# Pinout_DevKitC_Sch.net
KiCad netlist of a schematic drawn in Altium Designer
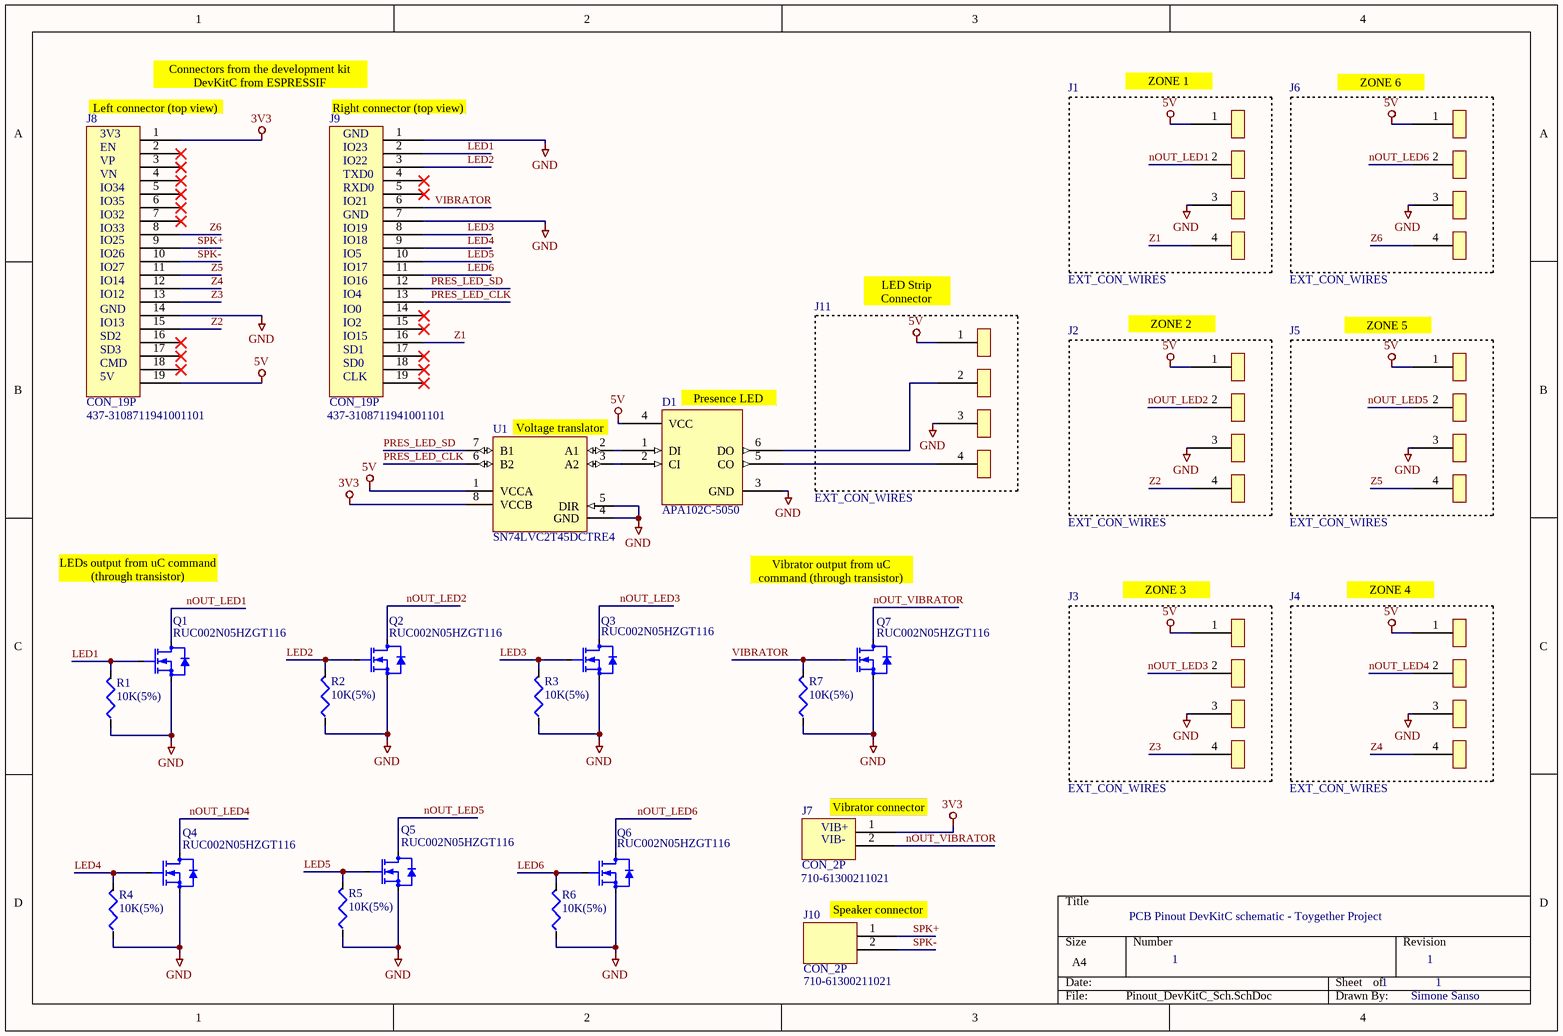
[diagram p0: Pinout_DevKitC_Sch.SchDoc]

(export (version "E")
  (design (tool "Eeschema 10.0.6"))
  (components
    (comp (ref "D1")
      (value "APA102C-5050")
      (footprint "APA102C-5050")
      (libsource (lib "Toygether_Schlib") (part "APA102C"))
    )
    (comp (ref "J1")
      (value "EXT_CON_WIRES")
      (footprint "EXT_CON_WIRES_4P")
      (description "Pads between pinout board and wires of the plush toy")
      (libsource (lib "Toygether_Schlib") (part "EXT_CON_WIRES"))
    )
    (comp (ref "J2")
      (value "EXT_CON_WIRES")
      (footprint "EXT_CON_WIRES_4P")
      (description "Pads between pinout board and wires of the plush toy")
      (libsource (lib "Toygether_Schlib") (part "EXT_CON_WIRES"))
    )
    (comp (ref "J3")
      (value "EXT_CON_WIRES")
      (footprint "EXT_CON_WIRES_4P")
      (description "Pads between pinout board and wires of the plush toy")
      (libsource (lib "Toygether_Schlib") (part "EXT_CON_WIRES"))
    )
    (comp (ref "J4")
      (value "EXT_CON_WIRES")
      (footprint "EXT_CON_WIRES_4P")
      (description "Pads between pinout board and wires of the plush toy")
      (libsource (lib "Toygether_Schlib") (part "EXT_CON_WIRES"))
    )
    (comp (ref "J5")
      (value "EXT_CON_WIRES")
      (footprint "EXT_CON_WIRES_4P")
      (description "Pads between pinout board and wires of the plush toy")
      (libsource (lib "Toygether_Schlib") (part "EXT_CON_WIRES"))
    )
    (comp (ref "J6")
      (value "EXT_CON_WIRES")
      (footprint "EXT_CON_WIRES_4P")
      (description "Pads between pinout board and wires of the plush toy")
      (libsource (lib "Toygether_Schlib") (part "EXT_CON_WIRES"))
    )
    (comp (ref "J7")
      (value "CON_2P")
      (footprint "CON_2P")
      (description "2 Positions Header, Breakaway Connector 0.100\" (2.54mm) Through Hole Tin")
      (fields (field (name "SUPPLIER PART NUMBER 1") "710-61300211021"))
      (libsource (lib "Toygether_Schlib") (part "CON_2P"))
    )
    (comp (ref "J8")
      (value "CON_19P")
      (footprint "CON_19P")
      (description "19 Positions Header, Breakaway Connector 0.100\" (2.54mm) Through Hole Tin")
      (fields (field (name "SUPPLIER PART NUMBER 1") "437-3108711941001101"))
      (libsource (lib "Toygether_Schlib") (part "CON_19P"))
    )
    (comp (ref "J9")
      (value "CON_19P")
      (footprint "CON_19P")
      (description "19 Positions Header, Breakaway Connector 0.100\" (2.54mm) Through Hole Tin")
      (fields (field (name "SUPPLIER PART NUMBER 1") "437-3108711941001101"))
      (libsource (lib "Toygether_Schlib") (part "CON_19P"))
    )
    (comp (ref "J10")
      (value "CON_2P")
      (footprint "CON_2P")
      (description "2 Positions Header, Breakaway Connector 0.100\" (2.54mm) Through Hole Tin")
      (fields (field (name "SUPPLIER PART NUMBER 1") "710-61300211021"))
      (libsource (lib "Toygether_Schlib") (part "CON_2P"))
    )
    (comp (ref "J11")
      (value "EXT_CON_WIRES")
      (footprint "EXT_CON_WIRES_4P")
      (description "Pads between pinout board and wires of the plush toy")
      (libsource (lib "Toygether_Schlib") (part "EXT_CON_WIRES"))
    )
    (comp (ref "Q1")
      (value "RUC002N05HZGT116")
      (footprint "MOS-N_RUC002N05")
      (description "RUC002N05HZGT116 (N-CH/50V/2.2R/200mA)")
      (libsource (lib "Toygether_Schlib") (part "MOSFET_N-CH_RUC002N05HZGT116"))
    )
    (comp (ref "Q2")
      (value "RUC002N05HZGT116")
      (footprint "MOS-N_RUC002N05")
      (description "RUC002N05HZGT116 (N-CH/50V/2.2R/200mA)")
      (libsource (lib "Toygether_Schlib") (part "MOSFET_N-CH_RUC002N05HZGT116"))
    )
    (comp (ref "Q3")
      (value "RUC002N05HZGT116")
      (footprint "MOS-N_RUC002N05")
      (description "RUC002N05HZGT116 (N-CH/50V/2.2R/200mA)")
      (libsource (lib "Toygether_Schlib") (part "MOSFET_N-CH_RUC002N05HZGT116"))
    )
    (comp (ref "Q4")
      (value "RUC002N05HZGT116")
      (footprint "MOS-N_RUC002N05")
      (description "RUC002N05HZGT116 (N-CH/50V/2.2R/200mA)")
      (libsource (lib "Toygether_Schlib") (part "MOSFET_N-CH_RUC002N05HZGT116"))
    )
    (comp (ref "Q5")
      (value "RUC002N05HZGT116")
      (footprint "MOS-N_RUC002N05")
      (description "RUC002N05HZGT116 (N-CH/50V/2.2R/200mA)")
      (libsource (lib "Toygether_Schlib") (part "MOSFET_N-CH_RUC002N05HZGT116"))
    )
    (comp (ref "Q6")
      (value "RUC002N05HZGT116")
      (footprint "MOS-N_RUC002N05")
      (description "RUC002N05HZGT116 (N-CH/50V/2.2R/200mA)")
      (libsource (lib "Toygether_Schlib") (part "MOSFET_N-CH_RUC002N05HZGT116"))
    )
    (comp (ref "Q7")
      (value "RUC002N05HZGT116")
      (footprint "MOS-N_RUC002N05")
      (description "RUC002N05HZGT116 (N-CH/50V/2.2R/200mA)")
      (libsource (lib "Toygether_Schlib") (part "MOSFET_N-CH_RUC002N05HZGT116"))
    )
    (comp (ref "R1")
      (value "10K(5%)")
      (footprint "RC0603")
      (description "RC0603JR-0710KL")
      (libsource (lib "Toygether_Schlib") (part "RES-10K(5%)"))
    )
    (comp (ref "R2")
      (value "10K(5%)")
      (footprint "RC0603")
      (description "RC0603JR-0710KL")
      (libsource (lib "Toygether_Schlib") (part "RES-10K(5%)"))
    )
    (comp (ref "R3")
      (value "10K(5%)")
      (footprint "RC0603")
      (description "RC0603JR-0710KL")
      (libsource (lib "Toygether_Schlib") (part "RES-10K(5%)"))
    )
    (comp (ref "R4")
      (value "10K(5%)")
      (footprint "RC0603")
      (description "RC0603JR-0710KL")
      (libsource (lib "Toygether_Schlib") (part "RES-10K(5%)"))
    )
    (comp (ref "R5")
      (value "10K(5%)")
      (footprint "RC0603")
      (description "RC0603JR-0710KL")
      (libsource (lib "Toygether_Schlib") (part "RES-10K(5%)"))
    )
    (comp (ref "R6")
      (value "10K(5%)")
      (footprint "RC0603")
      (description "RC0603JR-0710KL")
      (libsource (lib "Toygether_Schlib") (part "RES-10K(5%)"))
    )
    (comp (ref "R7")
      (value "10K(5%)")
      (footprint "RC0603")
      (description "RC0603JR-0710KL")
      (libsource (lib "Toygether_Schlib") (part "RES-10K(5%)"))
    )
    (comp (ref "U1")
      (value "SN74LVC2T45DCTRE4")
      (footprint "VOLTAGE_TRANSLATOR_3.3-5V")
      (description "Translation - Voltage Levels DUAL-BIT DUAL SUPPLY TRANSCEIVER")
      (libsource (lib "Toygether_Schlib") (part "VOLTAGE_TRANSLATOR_3.3-5V"))
    )
  )
  (nets
    (net (code "1") (name "/LED1") (class "Default")
      (node (ref "J9") (pin "2") (pinfunction "1_2") (pintype "passive"))
      (node (ref "Q1") (pin "1") (pinfunction "1_1") (pintype "passive"))
      (node (ref "R1") (pin "2") (pinfunction "2_2") (pintype "passive"))
    )
    (net (code "2") (name "/LED2") (class "Default")
      (node (ref "J9") (pin "3") (pinfunction "1_3") (pintype "passive"))
      (node (ref "Q2") (pin "1") (pinfunction "1_1") (pintype "passive"))
      (node (ref "R2") (pin "2") (pinfunction "2_2") (pintype "passive"))
    )
    (net (code "3") (name "/LED3") (class "Default")
      (node (ref "J9") (pin "8") (pinfunction "1_8") (pintype "passive"))
      (node (ref "Q3") (pin "1") (pinfunction "1_1") (pintype "passive"))
      (node (ref "R3") (pin "2") (pinfunction "2_2") (pintype "passive"))
    )
    (net (code "4") (name "/LED4") (class "Default")
      (node (ref "J9") (pin "9") (pinfunction "1_9") (pintype "passive"))
      (node (ref "Q4") (pin "1") (pinfunction "1_1") (pintype "passive"))
      (node (ref "R4") (pin "2") (pinfunction "2_2") (pintype "passive"))
    )
    (net (code "5") (name "/LED5") (class "Default")
      (node (ref "J9") (pin "10") (pinfunction "1_10") (pintype "passive"))
      (node (ref "Q5") (pin "1") (pinfunction "1_1") (pintype "passive"))
      (node (ref "R5") (pin "2") (pinfunction "2_2") (pintype "passive"))
    )
    (net (code "6") (name "/LED6") (class "Default")
      (node (ref "J9") (pin "11") (pinfunction "1_11") (pintype "passive"))
      (node (ref "Q6") (pin "1") (pinfunction "1_1") (pintype "passive"))
      (node (ref "R6") (pin "2") (pinfunction "2_2") (pintype "passive"))
    )
    (net (code "7") (name "/PRES_LED_CLK") (class "Default")
      (node (ref "J9") (pin "13") (pinfunction "1_13") (pintype "passive"))
      (node (ref "U1") (pin "6") (pinfunction "B2_6") (pintype "bidirectional"))
    )
    (net (code "8") (name "/PRES_LED_SD") (class "Default")
      (node (ref "J9") (pin "12") (pinfunction "1_12") (pintype "passive"))
      (node (ref "U1") (pin "7") (pinfunction "B1_7") (pintype "bidirectional"))
    )
    (net (code "9") (name "/SPK+") (class "Default")
      (node (ref "J10") (pin "1") (pinfunction "1_1") (pintype "passive"))
      (node (ref "J8") (pin "9") (pinfunction "1_9") (pintype "passive"))
    )
    (net (code "10") (name "/SPK-") (class "Default")
      (node (ref "J10") (pin "2") (pinfunction "2_2") (pintype "passive"))
      (node (ref "J8") (pin "10") (pinfunction "1_10") (pintype "passive"))
    )
    (net (code "11") (name "/VIBRATOR") (class "Default")
      (node (ref "J9") (pin "6") (pinfunction "1_6") (pintype "passive"))
      (node (ref "Q7") (pin "1") (pinfunction "1_1") (pintype "passive"))
      (node (ref "R7") (pin "2") (pinfunction "2_2") (pintype "passive"))
    )
    (net (code "12") (name "/Z1") (class "Default")
      (node (ref "J1") (pin "4") (pintype "passive"))
      (node (ref "J9") (pin "16") (pinfunction "1_16") (pintype "passive"))
    )
    (net (code "13") (name "/Z2") (class "Default")
      (node (ref "J2") (pin "4") (pintype "passive"))
      (node (ref "J8") (pin "15") (pinfunction "1_15") (pintype "passive"))
    )
    (net (code "14") (name "/Z3") (class "Default")
      (node (ref "J3") (pin "4") (pintype "passive"))
      (node (ref "J8") (pin "13") (pinfunction "1_13") (pintype "passive"))
    )
    (net (code "15") (name "/Z4") (class "Default")
      (node (ref "J4") (pin "4") (pintype "passive"))
      (node (ref "J8") (pin "12") (pinfunction "1_12") (pintype "passive"))
    )
    (net (code "16") (name "/Z5") (class "Default")
      (node (ref "J5") (pin "4") (pintype "passive"))
      (node (ref "J8") (pin "11") (pinfunction "1_11") (pintype "passive"))
    )
    (net (code "17") (name "/Z6") (class "Default")
      (node (ref "J6") (pin "4") (pintype "passive"))
      (node (ref "J8") (pin "8") (pinfunction "1_8") (pintype "passive"))
    )
    (net (code "18") (name "/nOUT_LED1") (class "Default")
      (node (ref "J1") (pin "2") (pintype "passive"))
      (node (ref "Q1") (pin "3") (pinfunction "3_3") (pintype "passive"))
    )
    (net (code "19") (name "/nOUT_LED2") (class "Default")
      (node (ref "J2") (pin "2") (pintype "passive"))
      (node (ref "Q2") (pin "3") (pinfunction "3_3") (pintype "passive"))
    )
    (net (code "20") (name "/nOUT_LED3") (class "Default")
      (node (ref "J3") (pin "2") (pintype "passive"))
      (node (ref "Q3") (pin "3") (pinfunction "3_3") (pintype "passive"))
    )
    (net (code "21") (name "/nOUT_LED4") (class "Default")
      (node (ref "J4") (pin "2") (pintype "passive"))
      (node (ref "Q4") (pin "3") (pinfunction "3_3") (pintype "passive"))
    )
    (net (code "22") (name "/nOUT_LED5") (class "Default")
      (node (ref "J5") (pin "2") (pintype "passive"))
      (node (ref "Q5") (pin "3") (pinfunction "3_3") (pintype "passive"))
    )
    (net (code "23") (name "/nOUT_LED6") (class "Default")
      (node (ref "J6") (pin "2") (pintype "passive"))
      (node (ref "Q6") (pin "3") (pinfunction "3_3") (pintype "passive"))
    )
    (net (code "24") (name "/nOUT_VIBRATOR") (class "Default")
      (node (ref "J7") (pin "2") (pinfunction "2_2") (pintype "passive"))
      (node (ref "Q7") (pin "3") (pinfunction "3_3") (pintype "passive"))
    )
    (net (code "25") (name "3V3") (class "Default")
      (node (ref "J7") (pin "1") (pinfunction "1_1") (pintype "passive"))
      (node (ref "J8") (pin "1") (pinfunction "1_1") (pintype "passive"))
      (node (ref "U1") (pin "8") (pinfunction "VCCB_8") (pintype "power_in"))
    )
    (net (code "26") (name "5V") (class "Default")
      (node (ref "D1") (pin "4") (pinfunction "VCC_4") (pintype "power_in"))
      (node (ref "J1") (pin "1") (pintype "passive"))
      (node (ref "J11") (pin "1") (pintype "passive"))
      (node (ref "J2") (pin "1") (pintype "passive"))
      (node (ref "J3") (pin "1") (pintype "passive"))
      (node (ref "J4") (pin "1") (pintype "passive"))
      (node (ref "J5") (pin "1") (pintype "passive"))
      (node (ref "J6") (pin "1") (pintype "passive"))
      (node (ref "J8") (pin "19") (pinfunction "1_19") (pintype "passive"))
      (node (ref "U1") (pin "1") (pinfunction "VCCA_1") (pintype "power_in"))
    )
    (net (code "27") (name "GND") (class "Default")
      (node (ref "D1") (pin "3") (pinfunction "GND_3") (pintype "power_in"))
      (node (ref "J1") (pin "3") (pintype "passive"))
      (node (ref "J11") (pin "3") (pintype "passive"))
      (node (ref "J2") (pin "3") (pintype "passive"))
      (node (ref "J3") (pin "3") (pintype "passive"))
      (node (ref "J4") (pin "3") (pintype "passive"))
      (node (ref "J5") (pin "3") (pintype "passive"))
      (node (ref "J6") (pin "3") (pintype "passive"))
      (node (ref "J8") (pin "14") (pinfunction "1_14") (pintype "passive"))
      (node (ref "J9") (pin "1") (pinfunction "1_1") (pintype "passive"))
      (node (ref "J9") (pin "7") (pinfunction "1_7") (pintype "passive"))
      (node (ref "Q1") (pin "2") (pinfunction "2_2") (pintype "passive"))
      (node (ref "Q2") (pin "2") (pinfunction "2_2") (pintype "passive"))
      (node (ref "Q3") (pin "2") (pinfunction "2_2") (pintype "passive"))
      (node (ref "Q4") (pin "2") (pinfunction "2_2") (pintype "passive"))
      (node (ref "Q5") (pin "2") (pinfunction "2_2") (pintype "passive"))
      (node (ref "Q6") (pin "2") (pinfunction "2_2") (pintype "passive"))
      (node (ref "Q7") (pin "2") (pinfunction "2_2") (pintype "passive"))
      (node (ref "R1") (pin "1") (pinfunction "1_1") (pintype "passive"))
      (node (ref "R2") (pin "1") (pinfunction "1_1") (pintype "passive"))
      (node (ref "R3") (pin "1") (pinfunction "1_1") (pintype "passive"))
      (node (ref "R4") (pin "1") (pinfunction "1_1") (pintype "passive"))
      (node (ref "R5") (pin "1") (pinfunction "1_1") (pintype "passive"))
      (node (ref "R6") (pin "1") (pinfunction "1_1") (pintype "passive"))
      (node (ref "R7") (pin "1") (pinfunction "1_1") (pintype "passive"))
      (node (ref "U1") (pin "4") (pinfunction "GND_4") (pintype "power_in"))
      (node (ref "U1") (pin "5") (pinfunction "DIR_5") (pintype "input"))
    )
    (net (code "28") (name "Net-(D1-CI)") (class "Default")
      (node (ref "D1") (pin "2") (pinfunction "CI_2") (pintype "input"))
      (node (ref "U1") (pin "3") (pinfunction "A2_3") (pintype "bidirectional"))
    )
    (net (code "29") (name "Net-(D1-CO)") (class "Default")
      (node (ref "D1") (pin "5") (pinfunction "CO_5") (pintype "output"))
      (node (ref "J11") (pin "4") (pintype "passive"))
    )
    (net (code "30") (name "Net-(D1-DI)") (class "Default")
      (node (ref "D1") (pin "1") (pinfunction "DI_1") (pintype "input"))
      (node (ref "U1") (pin "2") (pinfunction "A1_2") (pintype "bidirectional"))
    )
    (net (code "31") (name "Net-(D1-DO)") (class "Default")
      (node (ref "D1") (pin "6") (pinfunction "DO_6") (pintype "output"))
      (node (ref "J11") (pin "2") (pintype "passive"))
    )
    (net (code "32") (name "unconnected-(J8-1-Pad2)") (class "Default")
      (node (ref "J8") (pin "2") (pinfunction "1_2") (pintype "passive+no_connect"))
    )
    (net (code "33") (name "unconnected-(J8-1-Pad3)") (class "Default")
      (node (ref "J8") (pin "3") (pinfunction "1_3") (pintype "passive+no_connect"))
    )
    (net (code "34") (name "unconnected-(J8-1-Pad4)") (class "Default")
      (node (ref "J8") (pin "4") (pinfunction "1_4") (pintype "passive+no_connect"))
    )
    (net (code "35") (name "unconnected-(J8-1-Pad5)") (class "Default")
      (node (ref "J8") (pin "5") (pinfunction "1_5") (pintype "passive+no_connect"))
    )
    (net (code "36") (name "unconnected-(J8-1-Pad6)") (class "Default")
      (node (ref "J8") (pin "6") (pinfunction "1_6") (pintype "passive+no_connect"))
    )
    (net (code "37") (name "unconnected-(J8-1-Pad7)") (class "Default")
      (node (ref "J8") (pin "7") (pinfunction "1_7") (pintype "passive+no_connect"))
    )
    (net (code "38") (name "unconnected-(J8-1-Pad16)") (class "Default")
      (node (ref "J8") (pin "16") (pinfunction "1_16") (pintype "passive+no_connect"))
    )
    (net (code "39") (name "unconnected-(J8-1-Pad17)") (class "Default")
      (node (ref "J8") (pin "17") (pinfunction "1_17") (pintype "passive+no_connect"))
    )
    (net (code "40") (name "unconnected-(J8-1-Pad18)") (class "Default")
      (node (ref "J8") (pin "18") (pinfunction "1_18") (pintype "passive+no_connect"))
    )
    (net (code "41") (name "unconnected-(J9-1-Pad4)") (class "Default")
      (node (ref "J9") (pin "4") (pinfunction "1_4") (pintype "passive+no_connect"))
    )
    (net (code "42") (name "unconnected-(J9-1-Pad5)") (class "Default")
      (node (ref "J9") (pin "5") (pinfunction "1_5") (pintype "passive+no_connect"))
    )
    (net (code "43") (name "unconnected-(J9-1-Pad14)") (class "Default")
      (node (ref "J9") (pin "14") (pinfunction "1_14") (pintype "passive+no_connect"))
    )
    (net (code "44") (name "unconnected-(J9-1-Pad15)") (class "Default")
      (node (ref "J9") (pin "15") (pinfunction "1_15") (pintype "passive+no_connect"))
    )
    (net (code "45") (name "unconnected-(J9-1-Pad17)") (class "Default")
      (node (ref "J9") (pin "17") (pinfunction "1_17") (pintype "passive+no_connect"))
    )
    (net (code "46") (name "unconnected-(J9-1-Pad18)") (class "Default")
      (node (ref "J9") (pin "18") (pinfunction "1_18") (pintype "passive+no_connect"))
    )
    (net (code "47") (name "unconnected-(J9-1-Pad19)") (class "Default")
      (node (ref "J9") (pin "19") (pinfunction "1_19") (pintype "passive+no_connect"))
    )
  )
)
